# 3phasedriver.net
KiCad netlist of a schematic drawn in Altium Designer
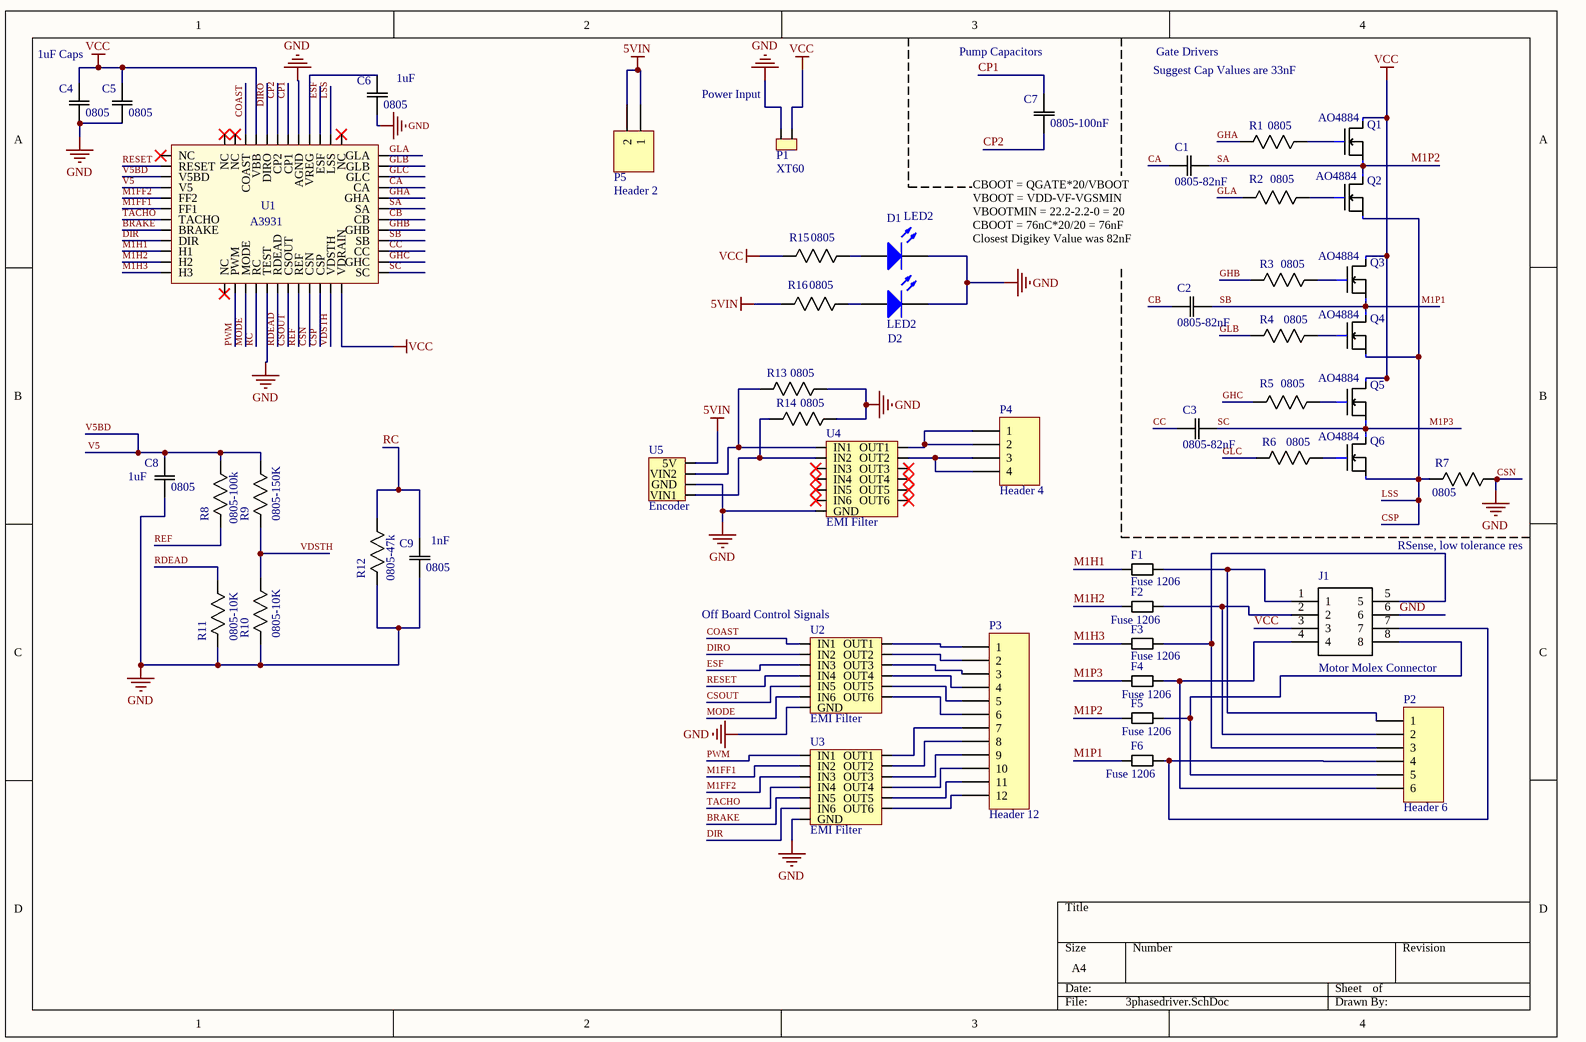
[diagram p0: 3phasedriver.SchDoc]

(export (version "E")
  (design (tool "Eeschema 10.0.6"))
  (components
    (comp (ref "C1")
      (value "0805-82nF")
      (footprint "CAPC2013X110N")
      (description "Capacitor; Ceramic; Cap; .100UF ; Tol+-10%; SMD; Vol-Rtg 50V; X7R, Tape/Reel")
      (fields (field (name "MP") "C0805C104K5RACTU") (field (name "MF") "Kemet"))
      (libsource (lib "100nF-C0805C104K5RACTU") (part "C0805C104K5RACTU"))
    )
    (comp (ref "C2")
      (value "0805-82nF")
      (footprint "CAPC2013X110N")
      (description "Capacitor; Ceramic; Cap; .100UF ; Tol+-10%; SMD; Vol-Rtg 50V; X7R, Tape/Reel")
      (fields (field (name "MP") "C0805C104K5RACTU") (field (name "MF") "Kemet"))
      (libsource (lib "100nF-C0805C104K5RACTU") (part "C0805C104K5RACTU"))
    )
    (comp (ref "C3")
      (value "0805-82nF")
      (footprint "CAPC2013X110N")
      (description "Capacitor; Ceramic; Cap; .100UF ; Tol+-10%; SMD; Vol-Rtg 50V; X7R, Tape/Reel")
      (fields (field (name "MP") "C0805C104K5RACTU") (field (name "MF") "Kemet"))
      (libsource (lib "100nF-C0805C104K5RACTU") (part "C0805C104K5RACTU"))
    )
    (comp (ref "C4")
      (value "0805")
      (footprint "CAPC2013X110N")
      (description "Capacitor; Ceramic; Cap; .100UF ; Tol+-10%; SMD; Vol-Rtg 50V; X7R, Tape/Reel")
      (fields (field (name "MP") "C0805C104K5RACTU") (field (name "MF") "Kemet"))
      (libsource (lib "") (part "C0805C104K5RACTU_1"))
    )
    (comp (ref "C5")
      (value "0805")
      (footprint "CAPC2013X110N")
      (description "Capacitor; Ceramic; Cap; .100UF ; Tol+-10%; SMD; Vol-Rtg 50V; X7R, Tape/Reel")
      (fields (field (name "MP") "C0805C104K5RACTU") (field (name "MF") "Kemet"))
      (libsource (lib "") (part "C0805C104K5RACTU_1"))
    )
    (comp (ref "C6")
      (value "0805")
      (footprint "CAPC2013X110N")
      (description "Capacitor; Ceramic; Cap; .100UF ; Tol+-10%; SMD; Vol-Rtg 50V; X7R, Tape/Reel")
      (fields (field (name "MP") "C0805C104K5RACTU") (field (name "MF") "Kemet"))
      (libsource (lib "") (part "C0805C104K5RACTU_1"))
    )
    (comp (ref "C7")
      (value "0805-100nF")
      (footprint "CAPC2013X110N")
      (description "Capacitor; Ceramic; Cap; .100UF ; Tol+-10%; SMD; Vol-Rtg 50V; X7R, Tape/Reel")
      (fields (field (name "MP") "C0805C104K5RACTU") (field (name "MF") "Kemet"))
      (libsource (lib "") (part "C0805C104K5RACTU_1"))
    )
    (comp (ref "C8")
      (value "0805")
      (footprint "CAPC2013X110N")
      (description "Capacitor; Ceramic; Cap; .100UF ; Tol+-10%; SMD; Vol-Rtg 50V; X7R, Tape/Reel")
      (fields (field (name "MP") "C0805C104K5RACTU") (field (name "MF") "Kemet"))
      (libsource (lib "") (part "C0805C104K5RACTU_1"))
    )
    (comp (ref "C9")
      (value "0805")
      (footprint "CAPC2013X110N")
      (description "Capacitor; Ceramic; Cap; .100UF ; Tol+-10%; SMD; Vol-Rtg 50V; X7R, Tape/Reel")
      (fields (field (name "MP") "C0805C104K5RACTU") (field (name "MF") "Kemet"))
      (libsource (lib "100nF-C0805C104K5RACTU") (part "C0805C104K5RACTU"))
    )
    (comp (ref "D1")
      (value "LED2")
      (footprint "3.2X1.6X1.1")
      (description "Typical RED, GREEN, YELLOW, AMBER GaAs LED")
      (fields (field (name "PUBLISHER") "Altium Limited"))
      (libsource (lib "Miscellaneous Devices") (part "LED2"))
    )
    (comp (ref "D2")
      (value "LED2")
      (footprint "3.2X1.6X1.1")
      (description "Typical RED, GREEN, YELLOW, AMBER GaAs LED")
      (fields (field (name "PUBLISHER") "Altium Limited"))
      (libsource (lib "Miscellaneous Devices") (part "LED2"))
    )
    (comp (ref "F1")
      (value "Fuse 1206")
      (footprint "PCBComponent_1")
      (libsource (lib "fuse_1206") (part "F?"))
    )
    (comp (ref "F2")
      (value "Fuse 1206")
      (footprint "PCBComponent_1")
      (libsource (lib "fuse_1206") (part "F?"))
    )
    (comp (ref "F3")
      (value "Fuse 1206")
      (footprint "PCBComponent_1")
      (libsource (lib "fuse_1206") (part "F?"))
    )
    (comp (ref "F4")
      (value "Fuse 1206")
      (footprint "PCBComponent_1")
      (libsource (lib "fuse_1206") (part "F?"))
    )
    (comp (ref "F5")
      (value "Fuse 1206")
      (footprint "PCBComponent_1")
      (libsource (lib "fuse_1206") (part "F?"))
    )
    (comp (ref "F6")
      (value "Fuse 1206")
      (footprint "PCBComponent_1")
      (libsource (lib "fuse_1206") (part "F?"))
    )
    (comp (ref "J1")
      (value "Motor Molex Connector")
      (footprint "*MOLEX_0039281083")
      (description "Conn Power HDR 8 POS 4.2mm Solder ST Thru-Hole 8 Terminal 1 Port Mini-Fit Jr??? Bag")
      (fields (field (name "MF") "Molex") (field (name "MP") "0039281083"))
      (libsource (lib "0039281083") (part "0039281083"))
    )
    (comp (ref "P1")
      (value "XT60")
      (footprint "PCBComponent_1")
      (libsource (lib "XT60") (part "Component_1"))
    )
    (comp (ref "P2")
      (value "Header 6")
      (footprint "HDR1X6")
      (description "Header, 6-Pin")
      (fields (field (name "PUBLISHER") "Altium Limited"))
      (libsource (lib "Miscellaneous Connectors") (part "Header 6"))
    )
    (comp (ref "P3")
      (value "Header 12")
      (footprint "HDR1X12")
      (description "Header, 12-Pin")
      (fields (field (name "PUBLISHER") "Altium Limited"))
      (libsource (lib "Miscellaneous Connectors") (part "Header 12"))
    )
    (comp (ref "P4")
      (value "Header 4")
      (footprint "HDR1X4")
      (description "Header, 4-Pin")
      (fields (field (name "PUBLISHER") "Altium Limited"))
      (libsource (lib "Miscellaneous Connectors") (part "Header 4"))
    )
    (comp (ref "P5")
      (value "Header 2")
      (footprint "HDR1X2")
      (description "Header, 2-Pin")
      (fields (field (name "PUBLISHER") "Altium Limited"))
      (libsource (lib "Miscellaneous Connectors") (part "Header 2"))
    )
    (comp (ref "Q1")
      (value "AO4884")
      (footprint "SOIC127P600X170-8N")
      (libsource (lib "") (part "Component_1_1"))
    )
    (comp (ref "Q2")
      (value "AO4884")
      (footprint "SOIC127P600X170-8N")
      (libsource (lib "AO4882") (part "Component_1"))
    )
    (comp (ref "Q3")
      (value "AO4884")
      (footprint "SOIC127P600X170-8N")
      (libsource (lib "AO4882") (part "Component_1"))
    )
    (comp (ref "Q4")
      (value "AO4884")
      (footprint "SOIC127P600X170-8N")
      (libsource (lib "AO4882") (part "Component_1"))
    )
    (comp (ref "Q5")
      (value "AO4884")
      (footprint "SOIC127P600X170-8N")
      (libsource (lib "AO4882") (part "Component_1"))
    )
    (comp (ref "Q6")
      (value "AO4884")
      (footprint "SOIC127P600X170-8N")
      (libsource (lib "AO4882") (part "Component_1"))
    )
    (comp (ref "R1")
      (value "0805")
      (footprint "RESC2013X65N")
      (description "Res Thick Film 0805 2.2K Ohm 1% 0.125W_1/8W_ Â}100ppm/ÂÂŽ Molded SMD Paper T/R")
      (fields (field (name "MP") "RC0805FR-072K2L") (field (name "MF") "Yageo"))
      (libsource (lib "") (part "RC0805FR-072K2L_1"))
    )
    (comp (ref "R2")
      (value "0805")
      (footprint "RESC2013X65N")
      (description "Res Thick Film 0805 2.2K Ohm 1% 0.125W_1/8W_ Â}100ppm/ÂÂŽ Molded SMD Paper T/R")
      (fields (field (name "MP") "RC0805FR-072K2L") (field (name "MF") "Yageo"))
      (libsource (lib "") (part "RC0805FR-072K2L_1"))
    )
    (comp (ref "R3")
      (value "0805")
      (footprint "RESC2013X65N")
      (description "Res Thick Film 0805 2.2K Ohm 1% 0.125W_1/8W_ Â}100ppm/ÂÂŽ Molded SMD Paper T/R")
      (fields (field (name "MP") "RC0805FR-072K2L") (field (name "MF") "Yageo"))
      (libsource (lib "") (part "RC0805FR-072K2L_1"))
    )
    (comp (ref "R4")
      (value "0805")
      (footprint "RESC2013X65N")
      (description "Res Thick Film 0805 2.2K Ohm 1% 0.125W_1/8W_ Â}100ppm/ÂÂŽ Molded SMD Paper T/R")
      (fields (field (name "MP") "RC0805FR-072K2L") (field (name "MF") "Yageo"))
      (libsource (lib "") (part "RC0805FR-072K2L_1"))
    )
    (comp (ref "R5")
      (value "0805")
      (footprint "RESC2013X65N")
      (description "Res Thick Film 0805 2.2K Ohm 1% 0.125W_1/8W_ Â}100ppm/ÂÂŽ Molded SMD Paper T/R")
      (fields (field (name "MP") "RC0805FR-072K2L") (field (name "MF") "Yageo"))
      (libsource (lib "") (part "RC0805FR-072K2L_1"))
    )
    (comp (ref "R6")
      (value "0805")
      (footprint "RESC2013X65N")
      (description "Res Thick Film 0805 2.2K Ohm 1% 0.125W_1/8W_ Â}100ppm/ÂÂŽ Molded SMD Paper T/R")
      (fields (field (name "MP") "RC0805FR-072K2L") (field (name "MF") "Yageo"))
      (libsource (lib "") (part "RC0805FR-072K2L_1"))
    )
    (comp (ref "R7")
      (value "0805")
      (footprint "RESC2013X65N")
      (description "Res Thick Film 0805 2.2K Ohm 1% 0.125W_1/8W_ Â}100ppm/ÂÂŽ Molded SMD Paper T/R")
      (fields (field (name "MP") "RC0805FR-072K2L") (field (name "MF") "Yageo"))
      (libsource (lib "") (part "RC0805FR-072K2L_3"))
    )
    (comp (ref "R8")
      (value "0805-100k")
      (footprint "RESC2013X65N")
      (description "Res Thick Film 0805 2.2K Ohm 1% 0.125W_1/8W_ Â}100ppm/ÂÂŽ Molded SMD Paper T/R")
      (fields (field (name "MP") "RC0805FR-072K2L") (field (name "MF") "Yageo"))
      (libsource (lib "RC0805FR-072K2L") (part "RC0805FR-072K2L"))
    )
    (comp (ref "R9")
      (value "0805-150K")
      (footprint "RESC2013X65N")
      (description "Res Thick Film 0805 2.2K Ohm 1% 0.125W_1/8W_ Â}100ppm/ÂÂŽ Molded SMD Paper T/R")
      (fields (field (name "MP") "RC0805FR-072K2L") (field (name "MF") "Yageo"))
      (libsource (lib "RC0805FR-072K2L") (part "RC0805FR-072K2L"))
    )
    (comp (ref "R10")
      (value "0805-10K")
      (footprint "RESC2013X65N")
      (description "Res Thick Film 0805 2.2K Ohm 1% 0.125W_1/8W_ Â}100ppm/ÂÂŽ Molded SMD Paper T/R")
      (fields (field (name "MP") "RC0805FR-072K2L") (field (name "MF") "Yageo"))
      (libsource (lib "RC0805FR-072K2L") (part "RC0805FR-072K2L"))
    )
    (comp (ref "R11")
      (value "0805-10K")
      (footprint "RESC2013X65N")
      (description "Res Thick Film 0805 2.2K Ohm 1% 0.125W_1/8W_ Â}100ppm/ÂÂŽ Molded SMD Paper T/R")
      (fields (field (name "MP") "RC0805FR-072K2L") (field (name "MF") "Yageo"))
      (libsource (lib "RC0805FR-072K2L") (part "RC0805FR-072K2L"))
    )
    (comp (ref "R12")
      (value "0805-47k")
      (footprint "RESC2013X65N")
      (description "Res Thick Film 0805 2.2K Ohm 1% 0.125W_1/8W_ Â}100ppm/ÂÂŽ Molded SMD Paper T/R")
      (fields (field (name "MP") "RC0805FR-072K2L") (field (name "MF") "Yageo"))
      (libsource (lib "") (part "RC0805FR-072K2L_2"))
    )
    (comp (ref "R13")
      (value "0805")
      (footprint "RESC2013X65N")
      (description "Res Thick Film 0805 2.2K Ohm 1% 0.125W_1/8W_ Â}100ppm/ÂÂŽ Molded SMD Paper T/R")
      (fields (field (name "MP") "RC0805FR-072K2L") (field (name "MF") "Yageo"))
      (libsource (lib "") (part "RC0805FR-072K2L_2"))
    )
    (comp (ref "R14")
      (value "0805")
      (footprint "RESC2013X65N")
      (description "Res Thick Film 0805 2.2K Ohm 1% 0.125W_1/8W_ Â}100ppm/ÂÂŽ Molded SMD Paper T/R")
      (fields (field (name "MP") "RC0805FR-072K2L") (field (name "MF") "Yageo"))
      (libsource (lib "") (part "RC0805FR-072K2L_2"))
    )
    (comp (ref "R15")
      (value "0805")
      (footprint "RESC2013X65N")
      (description "Res Thick Film 0805 2.2K Ohm 1% 0.125W_1/8W_ Â}100ppm/ÂÂŽ Molded SMD Paper T/R")
      (fields (field (name "MP") "RC0805FR-072K2L") (field (name "MF") "Yageo"))
      (libsource (lib "") (part "RC0805FR-072K2L_2"))
    )
    (comp (ref "R16")
      (value "0805")
      (footprint "RESC2013X65N")
      (description "Res Thick Film 0805 2.2K Ohm 1% 0.125W_1/8W_ Â}100ppm/ÂÂŽ Molded SMD Paper T/R")
      (fields (field (name "MP") "RC0805FR-072K2L") (field (name "MF") "Yageo"))
      (libsource (lib "") (part "RC0805FR-072K2L_2"))
    )
    (comp (ref "U1")
      (value "A3931")
      (footprint "CQFP50P900X900X160-48N")
      (libsource (lib "620-1289-1-ND") (part "Component_1"))
    )
    (comp (ref "U2")
      (value "EMI Filter")
      (footprint "Filter")
      (libsource (lib "497-7740-1-ND") (part "EMIFilter"))
    )
    (comp (ref "U3")
      (value "EMI Filter")
      (footprint "Filter")
      (libsource (lib "497-7740-1-ND") (part "EMIFilter"))
    )
    (comp (ref "U4")
      (value "EMI Filter")
      (footprint "Filter")
      (libsource (lib "497-7740-1-ND") (part "EMIFilter"))
    )
    (comp (ref "U5")
      (value "Encoder")
      (footprint "PCBComponent_1")
      (libsource (lib "Encoder_Connector") (part "Component_1"))
    )
  )
  (nets
    (net (code "1") (name "/BRAKE") (class "Default")
      (node (ref "U1") (pin "8") (pinfunction "BRAKE_8") (pintype "passive"))
      (node (ref "U3") (pin "5") (pinfunction "IN5_5") (pintype "passive"))
    )
    (net (code "2") (name "/CA") (class "Default")
      (node (ref "C1") (pin "1") (pinfunction "C1_1") (pintype "passive"))
      (node (ref "U1") (pin "33") (pinfunction "CA_33") (pintype "passive"))
    )
    (net (code "3") (name "/CB") (class "Default")
      (node (ref "C2") (pin "1") (pinfunction "C1_1") (pintype "passive"))
      (node (ref "U1") (pin "30") (pinfunction "CB_30") (pintype "passive"))
    )
    (net (code "4") (name "/CC") (class "Default")
      (node (ref "C3") (pin "1") (pinfunction "C1_1") (pintype "passive"))
      (node (ref "U1") (pin "27") (pinfunction "CC_27") (pintype "passive"))
    )
    (net (code "5") (name "/COAST") (class "Default")
      (node (ref "U1") (pin "46") (pinfunction "COAST_46") (pintype "passive"))
      (node (ref "U2") (pin "1") (pinfunction "IN1_1") (pintype "passive"))
    )
    (net (code "6") (name "/CP1") (class "Default")
      (node (ref "C7") (pin "2") (pinfunction "C2_2") (pintype "passive"))
      (node (ref "U1") (pin "42") (pinfunction "CP1_42") (pintype "passive"))
    )
    (net (code "7") (name "/CP2") (class "Default")
      (node (ref "C7") (pin "1") (pinfunction "C1_1") (pintype "passive"))
      (node (ref "U1") (pin "43") (pinfunction "CP2_43") (pintype "passive"))
    )
    (net (code "8") (name "/CSOUT") (class "Default")
      (node (ref "U1") (pin "19") (pinfunction "CSOUT_19") (pintype "passive"))
      (node (ref "U2") (pin "5") (pinfunction "IN5_5") (pintype "passive"))
    )
    (net (code "9") (name "/CSP") (class "Default")
      (node (ref "Q2") (pin "S") (pinfunction "S_S") (pintype "passive"))
      (node (ref "Q4") (pin "S") (pinfunction "S_S") (pintype "passive"))
      (node (ref "Q6") (pin "S") (pinfunction "S_S") (pintype "passive"))
      (node (ref "R7") (pin "2") (pinfunction "R2_2") (pintype "passive"))
      (node (ref "U1") (pin "22") (pinfunction "CSP_22") (pintype "passive"))
      (node (ref "U1") (pin "38") (pinfunction "LSS_38") (pintype "passive"))
    )
    (net (code "10") (name "/DIR") (class "Default")
      (node (ref "U1") (pin "9") (pinfunction "DIR_9") (pintype "passive"))
      (node (ref "U3") (pin "6") (pinfunction "IN6_6") (pintype "passive"))
    )
    (net (code "11") (name "/DIRO") (class "Default")
      (node (ref "U1") (pin "44") (pinfunction "DIRO_44") (pintype "passive"))
      (node (ref "U2") (pin "2") (pinfunction "IN2_2") (pintype "passive"))
    )
    (net (code "12") (name "/ESF") (class "Default")
      (node (ref "U1") (pin "39") (pinfunction "ESF_39") (pintype "passive"))
      (node (ref "U2") (pin "3") (pinfunction "IN3_3") (pintype "passive"))
    )
    (net (code "13") (name "/GHA") (class "Default")
      (node (ref "R1") (pin "2") (pinfunction "R2_2") (pintype "passive"))
      (node (ref "U1") (pin "32") (pinfunction "GHA_32") (pintype "passive"))
    )
    (net (code "14") (name "/GHB") (class "Default")
      (node (ref "R3") (pin "2") (pinfunction "R2_2") (pintype "passive"))
      (node (ref "U1") (pin "29") (pinfunction "GHB_29") (pintype "passive"))
    )
    (net (code "15") (name "/GHC") (class "Default")
      (node (ref "R5") (pin "2") (pinfunction "R2_2") (pintype "passive"))
      (node (ref "U1") (pin "26") (pinfunction "GHC_26") (pintype "passive"))
    )
    (net (code "16") (name "/GLA") (class "Default")
      (node (ref "R2") (pin "2") (pinfunction "R2_2") (pintype "passive"))
      (node (ref "U1") (pin "36") (pinfunction "GLA_36") (pintype "passive"))
    )
    (net (code "17") (name "/GLB") (class "Default")
      (node (ref "R4") (pin "2") (pinfunction "R2_2") (pintype "passive"))
      (node (ref "U1") (pin "35") (pinfunction "GLB_35") (pintype "passive"))
    )
    (net (code "18") (name "/GLC") (class "Default")
      (node (ref "R6") (pin "2") (pinfunction "R2_2") (pintype "passive"))
      (node (ref "U1") (pin "34") (pinfunction "GLC_34") (pintype "passive"))
    )
    (net (code "19") (name "/M1FF1") (class "Default")
      (node (ref "U1") (pin "6") (pinfunction "FF1_6") (pintype "passive"))
      (node (ref "U3") (pin "2") (pinfunction "IN2_2") (pintype "passive"))
    )
    (net (code "20") (name "/M1FF2") (class "Default")
      (node (ref "U1") (pin "5") (pinfunction "FF2_5") (pintype "passive"))
      (node (ref "U3") (pin "3") (pinfunction "IN3_3") (pintype "passive"))
    )
    (net (code "21") (name "/M1H1") (class "Default")
      (node (ref "F1") (pin "1") (pinfunction "1_1") (pintype "passive"))
      (node (ref "U1") (pin "10") (pinfunction "H1_10") (pintype "passive"))
    )
    (net (code "22") (name "/M1H2") (class "Default")
      (node (ref "F2") (pin "1") (pinfunction "1_1") (pintype "passive"))
      (node (ref "U1") (pin "11") (pinfunction "H2_11") (pintype "passive"))
    )
    (net (code "23") (name "/M1H3") (class "Default")
      (node (ref "F3") (pin "1") (pinfunction "1_1") (pintype "passive"))
      (node (ref "U1") (pin "12") (pinfunction "H3_12") (pintype "passive"))
    )
    (net (code "24") (name "/M1P1") (class "Default")
      (node (ref "C2") (pin "2") (pinfunction "C2_2") (pintype "passive"))
      (node (ref "F6") (pin "1") (pinfunction "1_1") (pintype "passive"))
      (node (ref "Q3") (pin "S") (pinfunction "S_S") (pintype "passive"))
      (node (ref "Q4") (pin "D") (pinfunction "D_D") (pintype "passive"))
      (node (ref "U1") (pin "28") (pinfunction "SB_28") (pintype "passive"))
    )
    (net (code "25") (name "/M1P2") (class "Default")
      (node (ref "C1") (pin "2") (pinfunction "C2_2") (pintype "passive"))
      (node (ref "F5") (pin "1") (pinfunction "1_1") (pintype "passive"))
      (node (ref "Q1") (pin "S") (pinfunction "S_S") (pintype "passive"))
      (node (ref "Q2") (pin "D") (pinfunction "D_D") (pintype "passive"))
      (node (ref "U1") (pin "31") (pinfunction "SA_31") (pintype "passive"))
    )
    (net (code "26") (name "/M1P3") (class "Default")
      (node (ref "C3") (pin "2") (pinfunction "C2_2") (pintype "passive"))
      (node (ref "F4") (pin "1") (pinfunction "1_1") (pintype "passive"))
      (node (ref "Q5") (pin "S") (pinfunction "S_S") (pintype "passive"))
      (node (ref "Q6") (pin "D") (pinfunction "D_D") (pintype "passive"))
      (node (ref "U1") (pin "25") (pinfunction "SC_25") (pintype "passive"))
    )
    (net (code "27") (name "/MODE") (class "Default")
      (node (ref "U1") (pin "15") (pinfunction "MODE_15") (pintype "passive"))
      (node (ref "U2") (pin "6") (pinfunction "IN6_6") (pintype "passive"))
    )
    (net (code "28") (name "/PWM") (class "Default")
      (node (ref "U1") (pin "14") (pinfunction "PWM_14") (pintype "passive"))
      (node (ref "U3") (pin "1") (pinfunction "IN1_1") (pintype "passive"))
    )
    (net (code "29") (name "/RC") (class "Default")
      (node (ref "C9") (pin "2") (pinfunction "C2_2") (pintype "passive"))
      (node (ref "R12") (pin "1") (pinfunction "R1_1") (pintype "passive"))
      (node (ref "U1") (pin "16") (pinfunction "RC_16") (pintype "passive"))
    )
    (net (code "30") (name "/RDEAD") (class "Default")
      (node (ref "R11") (pin "1") (pinfunction "R1_1") (pintype "passive"))
      (node (ref "U1") (pin "18") (pinfunction "RDEAD_18") (pintype "passive"))
    )
    (net (code "31") (name "/REF") (class "Default")
      (node (ref "R8") (pin "2") (pinfunction "R2_2") (pintype "passive"))
      (node (ref "U1") (pin "20") (pinfunction "REF_20") (pintype "passive"))
    )
    (net (code "32") (name "/RESET") (class "Default")
      (node (ref "U1") (pin "2") (pinfunction "RESET_2") (pintype "passive"))
      (node (ref "U2") (pin "4") (pinfunction "IN4_4") (pintype "passive"))
    )
    (net (code "33") (name "/TACHO") (class "Default")
      (node (ref "U1") (pin "7") (pinfunction "TACHO_7") (pintype "passive"))
      (node (ref "U3") (pin "4") (pinfunction "IN4_4") (pintype "passive"))
    )
    (net (code "34") (name "/V5") (class "Default")
      (node (ref "C8") (pin "2") (pinfunction "C2_2") (pintype "passive"))
      (node (ref "R8") (pin "1") (pinfunction "R1_1") (pintype "passive"))
      (node (ref "R9") (pin "1") (pinfunction "R1_1") (pintype "passive"))
      (node (ref "U1") (pin "3") (pinfunction "V5BD_3") (pintype "passive"))
      (node (ref "U1") (pin "4") (pinfunction "V5_4") (pintype "passive"))
    )
    (net (code "35") (name "/VDSTH") (class "Default")
      (node (ref "R10") (pin "1") (pinfunction "R1_1") (pintype "passive"))
      (node (ref "R9") (pin "2") (pinfunction "R2_2") (pintype "passive"))
      (node (ref "U1") (pin "23") (pinfunction "VDSTH_23") (pintype "passive"))
    )
    (net (code "36") (name "5VIN") (class "Default")
      (node (ref "P5") (pin "1") (pinfunction "1_1") (pintype "passive"))
      (node (ref "P5") (pin "2") (pinfunction "2_2") (pintype "passive"))
      (node (ref "R16") (pin "2") (pinfunction "R2_2") (pintype "passive"))
      (node (ref "U5") (pin "5V") (pinfunction "5V_5V") (pintype "passive"))
    )
    (net (code "37") (name "GND") (class "Default")
      (node (ref "C4") (pin "1") (pinfunction "C1_1") (pintype "passive"))
      (node (ref "C5") (pin "1") (pinfunction "C1_1") (pintype "passive"))
      (node (ref "C6") (pin "1") (pinfunction "C1_1") (pintype "passive"))
      (node (ref "C8") (pin "1") (pinfunction "C1_1") (pintype "passive"))
      (node (ref "C9") (pin "1") (pinfunction "C1_1") (pintype "passive"))
      (node (ref "D1") (pin "2") (pinfunction "K_2") (pintype "passive"))
      (node (ref "D2") (pin "2") (pinfunction "K_2") (pintype "passive"))
      (node (ref "J1") (pin "6") (pinfunction "6_6") (pintype "passive"))
      (node (ref "P1") (pin "2") (pinfunction "2_2") (pintype "passive"))
      (node (ref "R10") (pin "2") (pinfunction "R2_2") (pintype "passive"))
      (node (ref "R11") (pin "2") (pinfunction "R2_2") (pintype "passive"))
      (node (ref "R12") (pin "2") (pinfunction "R2_2") (pintype "passive"))
      (node (ref "R13") (pin "1") (pinfunction "R1_1") (pintype "passive"))
      (node (ref "R14") (pin "1") (pinfunction "R1_1") (pintype "passive"))
      (node (ref "R7") (pin "1") (pinfunction "R1_1") (pintype "passive"))
      (node (ref "U1") (pin "17") (pinfunction "TEST_17") (pintype "passive"))
      (node (ref "U1") (pin "21") (pinfunction "CSN_21") (pintype "passive"))
      (node (ref "U1") (pin "41") (pinfunction "AGND_41") (pintype "passive"))
      (node (ref "U2") (pin "GND") (pinfunction "GND_GND") (pintype "passive"))
      (node (ref "U3") (pin "GND") (pinfunction "GND_GND") (pintype "passive"))
      (node (ref "U4") (pin "GND") (pinfunction "GND_GND") (pintype "passive"))
      (node (ref "U5") (pin "GND") (pinfunction "GND_GND") (pintype "passive"))
    )
    (net (code "38") (name "Net-(C6-C2)") (class "Default")
      (node (ref "C6") (pin "2") (pinfunction "C2_2") (pintype "passive"))
      (node (ref "U1") (pin "40") (pinfunction "VREG_40") (pintype "passive"))
    )
    (net (code "39") (name "Net-(D1-A)") (class "Default")
      (node (ref "D1") (pin "1") (pinfunction "A_1") (pintype "passive"))
      (node (ref "R15") (pin "1") (pinfunction "R1_1") (pintype "passive"))
    )
    (net (code "40") (name "Net-(D2-A)") (class "Default")
      (node (ref "D2") (pin "1") (pinfunction "A_1") (pintype "passive"))
      (node (ref "R16") (pin "1") (pinfunction "R1_1") (pintype "passive"))
    )
    (net (code "41") (name "Net-(F1-Pad2)") (class "Default")
      (node (ref "F1") (pin "2") (pinfunction "2_2") (pintype "passive"))
      (node (ref "J1") (pin "1") (pinfunction "1_1") (pintype "passive"))
      (node (ref "P2") (pin "1") (pinfunction "1_1") (pintype "passive"))
    )
    (net (code "42") (name "Net-(F2-Pad2)") (class "Default")
      (node (ref "F2") (pin "2") (pinfunction "2_2") (pintype "passive"))
      (node (ref "J1") (pin "2") (pinfunction "2_2") (pintype "passive"))
      (node (ref "P2") (pin "2") (pinfunction "2_2") (pintype "passive"))
    )
    (net (code "43") (name "Net-(F3-Pad2)") (class "Default")
      (node (ref "F3") (pin "2") (pinfunction "2_2") (pintype "passive"))
      (node (ref "J1") (pin "5") (pinfunction "5_5") (pintype "passive"))
      (node (ref "P2") (pin "3") (pinfunction "3_3") (pintype "passive"))
    )
    (net (code "44") (name "Net-(F4-Pad2)") (class "Default")
      (node (ref "F4") (pin "2") (pinfunction "2_2") (pintype "passive"))
      (node (ref "J1") (pin "4") (pinfunction "4_4") (pintype "passive"))
      (node (ref "P2") (pin "6") (pinfunction "6_6") (pintype "passive"))
    )
    (net (code "45") (name "Net-(F5-Pad2)") (class "Default")
      (node (ref "F5") (pin "2") (pinfunction "2_2") (pintype "passive"))
      (node (ref "J1") (pin "8") (pinfunction "8_8") (pintype "passive"))
      (node (ref "P2") (pin "5") (pinfunction "5_5") (pintype "passive"))
    )
    (net (code "46") (name "Net-(F6-Pad2)") (class "Default")
      (node (ref "F6") (pin "2") (pinfunction "2_2") (pintype "passive"))
      (node (ref "J1") (pin "7") (pinfunction "7_7") (pintype "passive"))
      (node (ref "P2") (pin "4") (pinfunction "4_4") (pintype "passive"))
    )
    (net (code "47") (name "Net-(R1-R1)") (class "Default")
      (node (ref "Q1") (pin "G") (pinfunction "G_G") (pintype "passive"))
      (node (ref "R1") (pin "1") (pinfunction "R1_1") (pintype "passive"))
    )
    (net (code "48") (name "Net-(R2-R1)") (class "Default")
      (node (ref "Q2") (pin "G") (pinfunction "G_G") (pintype "passive"))
      (node (ref "R2") (pin "1") (pinfunction "R1_1") (pintype "passive"))
    )
    (net (code "49") (name "Net-(R3-R1)") (class "Default")
      (node (ref "Q3") (pin "G") (pinfunction "G_G") (pintype "passive"))
      (node (ref "R3") (pin "1") (pinfunction "R1_1") (pintype "passive"))
    )
    (net (code "50") (name "Net-(R4-R1)") (class "Default")
      (node (ref "Q4") (pin "G") (pinfunction "G_G") (pintype "passive"))
      (node (ref "R4") (pin "1") (pinfunction "R1_1") (pintype "passive"))
    )
    (net (code "51") (name "Net-(R5-R1)") (class "Default")
      (node (ref "Q5") (pin "G") (pinfunction "G_G") (pintype "passive"))
      (node (ref "R5") (pin "1") (pinfunction "R1_1") (pintype "passive"))
    )
    (net (code "52") (name "Net-(R6-R1)") (class "Default")
      (node (ref "Q6") (pin "G") (pinfunction "G_G") (pintype "passive"))
      (node (ref "R6") (pin "1") (pinfunction "R1_1") (pintype "passive"))
    )
    (net (code "53") (name "Net-(R13-R2)") (class "Default")
      (node (ref "R13") (pin "2") (pinfunction "R2_2") (pintype "passive"))
      (node (ref "U4") (pin "1") (pinfunction "IN1_1") (pintype "passive"))
      (node (ref "U5") (pin "VIN2") (pinfunction "VIN2_VIN2") (pintype "passive"))
    )
    (net (code "54") (name "Net-(R14-R2)") (class "Default")
      (node (ref "R14") (pin "2") (pinfunction "R2_2") (pintype "passive"))
      (node (ref "U4") (pin "2") (pinfunction "IN2_2") (pintype "passive"))
      (node (ref "U5") (pin "VIN1") (pinfunction "VIN1_VIN1") (pintype "passive"))
    )
    (net (code "55") (name "Net-(U2-OUT1)") (class "Default")
      (node (ref "P3") (pin "1") (pinfunction "1_1") (pintype "passive"))
      (node (ref "U2") (pin "7") (pinfunction "OUT1_7") (pintype "passive"))
    )
    (net (code "56") (name "Net-(U2-OUT2)") (class "Default")
      (node (ref "P3") (pin "2") (pinfunction "2_2") (pintype "passive"))
      (node (ref "U2") (pin "8") (pinfunction "OUT2_8") (pintype "passive"))
    )
    (net (code "57") (name "Net-(U2-OUT3)") (class "Default")
      (node (ref "P3") (pin "3") (pinfunction "3_3") (pintype "passive"))
      (node (ref "U2") (pin "9") (pinfunction "OUT3_9") (pintype "passive"))
    )
    (net (code "58") (name "Net-(U2-OUT4)") (class "Default")
      (node (ref "P3") (pin "4") (pinfunction "4_4") (pintype "passive"))
      (node (ref "U2") (pin "10") (pinfunction "OUT4_10") (pintype "passive"))
    )
    (net (code "59") (name "Net-(U2-OUT5)") (class "Default")
      (node (ref "P3") (pin "5") (pinfunction "5_5") (pintype "passive"))
      (node (ref "U2") (pin "11") (pinfunction "OUT5_11") (pintype "passive"))
    )
    (net (code "60") (name "Net-(U2-OUT6)") (class "Default")
      (node (ref "P3") (pin "6") (pinfunction "6_6") (pintype "passive"))
      (node (ref "U2") (pin "12") (pinfunction "OUT6_12") (pintype "passive"))
    )
    (net (code "61") (name "Net-(U3-OUT1)") (class "Default")
      (node (ref "P3") (pin "7") (pinfunction "7_7") (pintype "passive"))
      (node (ref "U3") (pin "7") (pinfunction "OUT1_7") (pintype "passive"))
    )
    (net (code "62") (name "Net-(U3-OUT2)") (class "Default")
      (node (ref "P3") (pin "8") (pinfunction "8_8") (pintype "passive"))
      (node (ref "U3") (pin "8") (pinfunction "OUT2_8") (pintype "passive"))
    )
    (net (code "63") (name "Net-(U3-OUT3)") (class "Default")
      (node (ref "P3") (pin "9") (pinfunction "9_9") (pintype "passive"))
      (node (ref "U3") (pin "9") (pinfunction "OUT3_9") (pintype "passive"))
    )
    (net (code "64") (name "Net-(U3-OUT4)") (class "Default")
      (node (ref "P3") (pin "10") (pinfunction "10_10") (pintype "passive"))
      (node (ref "U3") (pin "10") (pinfunction "OUT4_10") (pintype "passive"))
    )
    (net (code "65") (name "Net-(U3-OUT5)") (class "Default")
      (node (ref "P3") (pin "11") (pinfunction "11_11") (pintype "passive"))
      (node (ref "U3") (pin "11") (pinfunction "OUT5_11") (pintype "passive"))
    )
    (net (code "66") (name "Net-(U3-OUT6)") (class "Default")
      (node (ref "P3") (pin "12") (pinfunction "12_12") (pintype "passive"))
      (node (ref "U3") (pin "12") (pinfunction "OUT6_12") (pintype "passive"))
    )
    (net (code "67") (name "Net-(U4-OUT1)") (class "Default")
      (node (ref "P4") (pin "1") (pinfunction "1_1") (pintype "passive"))
      (node (ref "P4") (pin "2") (pinfunction "2_2") (pintype "passive"))
      (node (ref "U4") (pin "7") (pinfunction "OUT1_7") (pintype "passive"))
    )
    (net (code "68") (name "Net-(U4-OUT2)") (class "Default")
      (node (ref "P4") (pin "3") (pinfunction "3_3") (pintype "passive"))
      (node (ref "P4") (pin "4") (pinfunction "4_4") (pintype "passive"))
      (node (ref "U4") (pin "8") (pinfunction "OUT2_8") (pintype "passive"))
    )
    (net (code "69") (name "VCC") (class "Default")
      (node (ref "C4") (pin "2") (pinfunction "C2_2") (pintype "passive"))
      (node (ref "C5") (pin "2") (pinfunction "C2_2") (pintype "passive"))
      (node (ref "J1") (pin "3") (pinfunction "3_3") (pintype "passive"))
      (node (ref "P1") (pin "1") (pinfunction "1_1") (pintype "passive"))
      (node (ref "Q1") (pin "D") (pinfunction "D_D") (pintype "passive"))
      (node (ref "Q3") (pin "D") (pinfunction "D_D") (pintype "passive"))
      (node (ref "Q5") (pin "D") (pinfunction "D_D") (pintype "passive"))
      (node (ref "R15") (pin "2") (pinfunction "R2_2") (pintype "passive"))
      (node (ref "U1") (pin "24") (pinfunction "VDRAIN_24") (pintype "passive"))
      (node (ref "U1") (pin "45") (pinfunction "VBB_45") (pintype "passive"))
    )
    (net (code "70") (name "unconnected-(U1-NC-Pad1)") (class "Default")
      (node (ref "U1") (pin "1") (pinfunction "NC_1") (pintype "passive+no_connect"))
    )
    (net (code "71") (name "unconnected-(U1-NC-Pad13)") (class "Default")
      (node (ref "U1") (pin "13") (pinfunction "NC_13") (pintype "passive+no_connect"))
    )
    (net (code "72") (name "unconnected-(U1-NC-Pad37)") (class "Default")
      (node (ref "U1") (pin "37") (pinfunction "NC_37") (pintype "passive+no_connect"))
    )
    (net (code "73") (name "unconnected-(U1-NC-Pad47)") (class "Default")
      (node (ref "U1") (pin "47") (pinfunction "NC_47") (pintype "passive+no_connect"))
    )
    (net (code "74") (name "unconnected-(U1-NC-Pad48)") (class "Default")
      (node (ref "U1") (pin "48") (pinfunction "NC_48") (pintype "passive+no_connect"))
    )
    (net (code "75") (name "unconnected-(U4-IN3-Pad3)") (class "Default")
      (node (ref "U4") (pin "3") (pinfunction "IN3_3") (pintype "passive+no_connect"))
    )
    (net (code "76") (name "unconnected-(U4-IN4-Pad4)") (class "Default")
      (node (ref "U4") (pin "4") (pinfunction "IN4_4") (pintype "passive+no_connect"))
    )
    (net (code "77") (name "unconnected-(U4-IN5-Pad5)") (class "Default")
      (node (ref "U4") (pin "5") (pinfunction "IN5_5") (pintype "passive+no_connect"))
    )
    (net (code "78") (name "unconnected-(U4-IN6-Pad6)") (class "Default")
      (node (ref "U4") (pin "6") (pinfunction "IN6_6") (pintype "passive+no_connect"))
    )
    (net (code "79") (name "unconnected-(U4-OUT3-Pad9)") (class "Default")
      (node (ref "U4") (pin "9") (pinfunction "OUT3_9") (pintype "passive+no_connect"))
    )
    (net (code "80") (name "unconnected-(U4-OUT4-Pad10)") (class "Default")
      (node (ref "U4") (pin "10") (pinfunction "OUT4_10") (pintype "passive+no_connect"))
    )
    (net (code "81") (name "unconnected-(U4-OUT5-Pad11)") (class "Default")
      (node (ref "U4") (pin "11") (pinfunction "OUT5_11") (pintype "passive+no_connect"))
    )
    (net (code "82") (name "unconnected-(U4-OUT6-Pad12)") (class "Default")
      (node (ref "U4") (pin "12") (pinfunction "OUT6_12") (pintype "passive+no_connect"))
    )
  )
)
